# adc-dac.net
KiCad netlist of a schematic drawn in Altium Designer
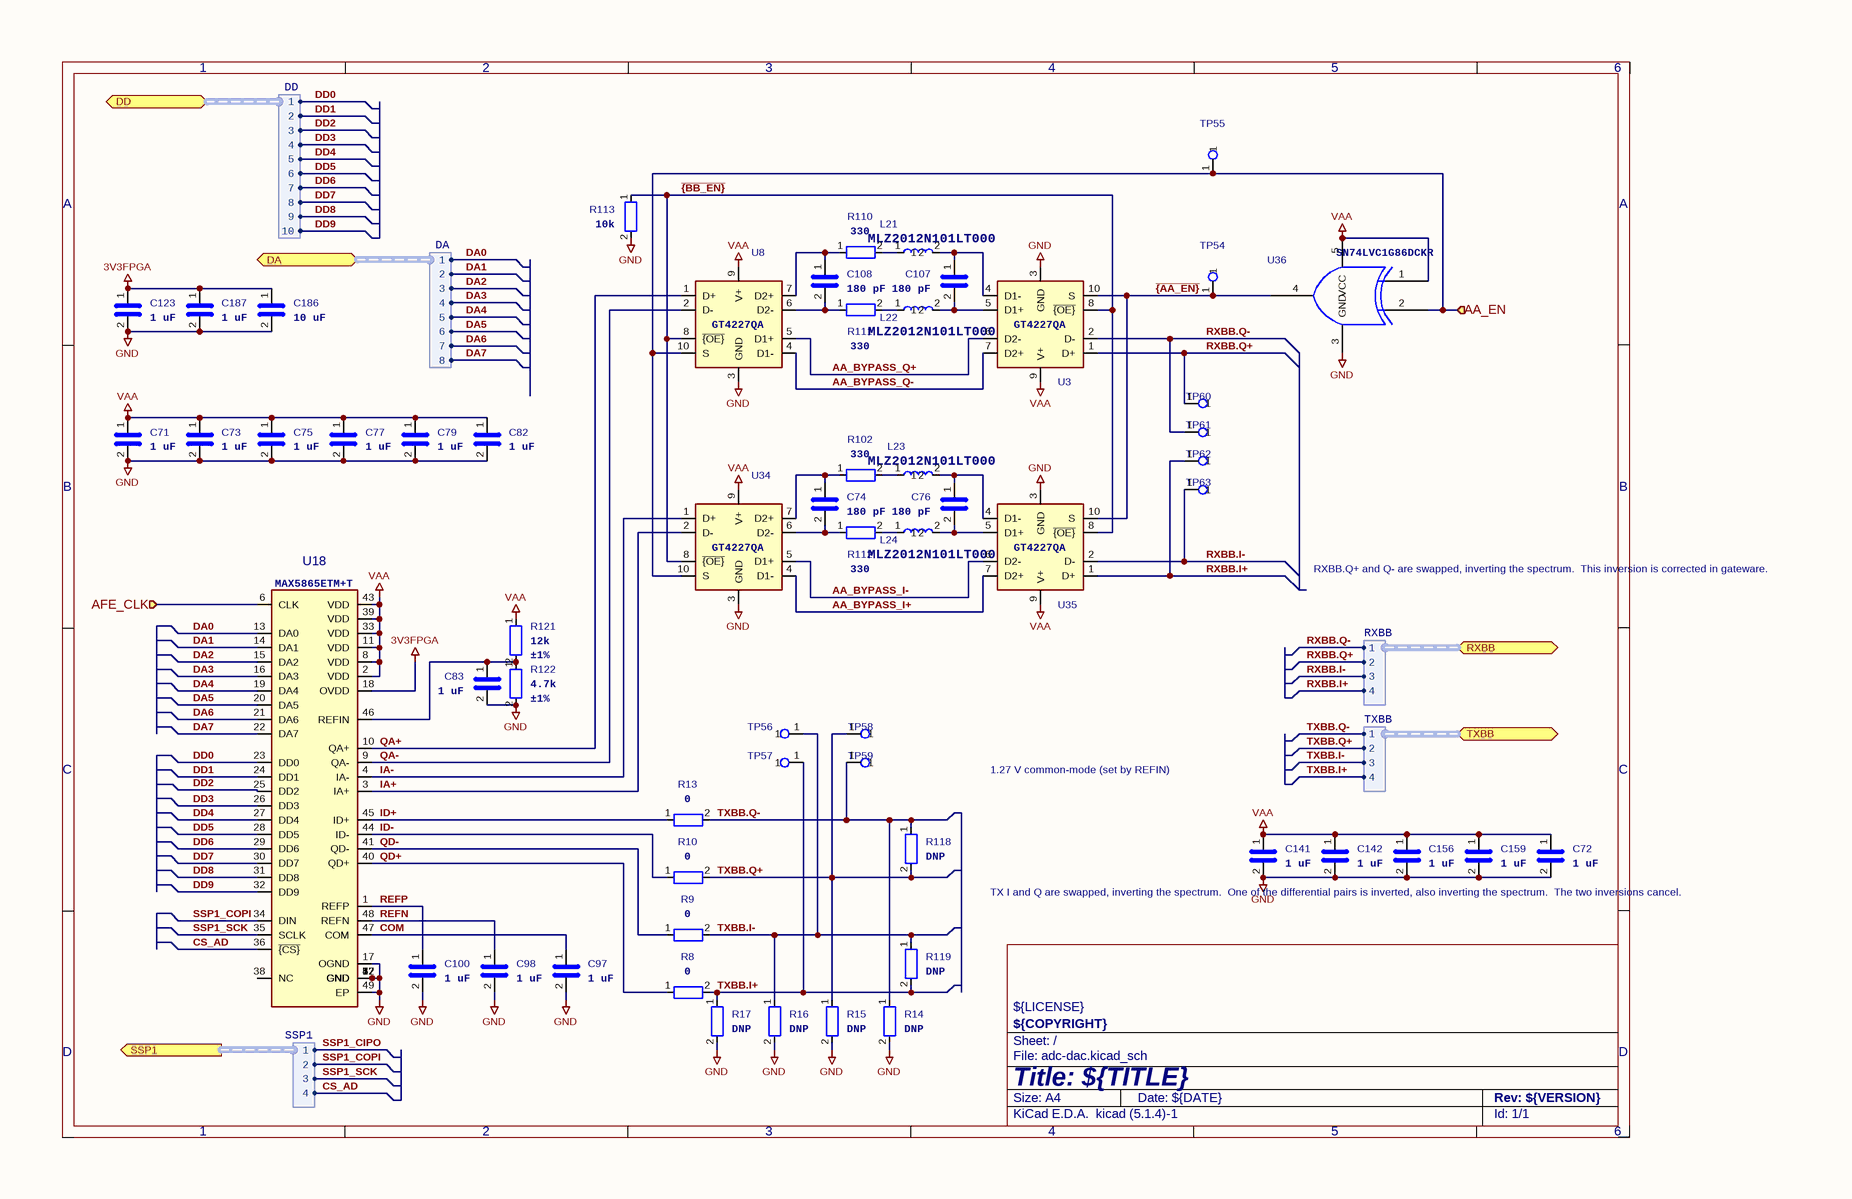
[diagram p0: adc-dac.SchDoc]

(export (version "E")
  (design (tool "Eeschema 10.0.6"))
  (components
    (comp (ref "C71")
      (value "1 uF")
      (footprint "C_0201_0603Metric")
      (fields (field (name "MANUFACTURER") "Murata") (field (name "PART NUMBER") "GRM033R61A105ME44D"))
      (libsource (lib "Device") (part "C"))
    )
    (comp (ref "C72")
      (value "1 uF")
      (footprint "C_0201_0603Metric")
      (fields (field (name "MANUFACTURER") "Murata") (field (name "PART NUMBER") "GRM033R61A105ME44D"))
      (libsource (lib "Device") (part "C"))
    )
    (comp (ref "C73")
      (value "1 uF")
      (footprint "C_0201_0603Metric")
      (fields (field (name "MANUFACTURER") "Murata") (field (name "PART NUMBER") "GRM033R61A105ME44D"))
      (libsource (lib "Device") (part "C"))
    )
    (comp (ref "C74")
      (value "180 pF")
      (footprint "C_0201_0603Metric")
      (fields (field (name "MANUFACTURER") "Murata") (field (name "PART NUMBER") "GRM0335C1H181JA01D"))
      (libsource (lib "Device") (part "C"))
    )
    (comp (ref "C75")
      (value "1 uF")
      (footprint "C_0201_0603Metric")
      (fields (field (name "MANUFACTURER") "Murata") (field (name "PART NUMBER") "GRM033R61A105ME44D"))
      (libsource (lib "Device") (part "C"))
    )
    (comp (ref "C76")
      (value "180 pF")
      (footprint "C_0201_0603Metric")
      (fields (field (name "MANUFACTURER") "Murata") (field (name "PART NUMBER") "GRM0335C1H181JA01D"))
      (libsource (lib "Device") (part "C"))
    )
    (comp (ref "C77")
      (value "1 uF")
      (footprint "C_0201_0603Metric")
      (fields (field (name "MANUFACTURER") "Murata") (field (name "PART NUMBER") "GRM033R61A105ME44D"))
      (libsource (lib "Device") (part "C"))
    )
    (comp (ref "C79")
      (value "1 uF")
      (footprint "C_0201_0603Metric")
      (fields (field (name "MANUFACTURER") "Murata") (field (name "PART NUMBER") "GRM033R61A105ME44D"))
      (libsource (lib "Device") (part "C"))
    )
    (comp (ref "C82")
      (value "1 uF")
      (footprint "C_0201_0603Metric")
      (fields (field (name "MANUFACTURER") "Murata") (field (name "PART NUMBER") "GRM033R61A105ME44D"))
      (libsource (lib "Device") (part "C"))
    )
    (comp (ref "C83")
      (value "1 uF")
      (footprint "C_0201_0603Metric")
      (fields (field (name "MANUFACTURER") "Murata") (field (name "PART NUMBER") "GRM033R61A105ME44D"))
      (libsource (lib "Device") (part "C"))
    )
    (comp (ref "C97")
      (value "1 uF")
      (footprint "C_0201_0603Metric")
      (fields (field (name "MANUFACTURER") "Murata") (field (name "PART NUMBER") "GRM033R61A105ME44D"))
      (libsource (lib "Device") (part "C"))
    )
    (comp (ref "C98")
      (value "1 uF")
      (footprint "C_0201_0603Metric")
      (fields (field (name "MANUFACTURER") "Murata") (field (name "PART NUMBER") "GRM033R61A105ME44D"))
      (libsource (lib "Device") (part "C"))
    )
    (comp (ref "C100")
      (value "1 uF")
      (footprint "C_0201_0603Metric")
      (fields (field (name "MANUFACTURER") "Murata") (field (name "PART NUMBER") "GRM033R61A105ME44D"))
      (libsource (lib "Device") (part "C"))
    )
    (comp (ref "C107")
      (value "180 pF")
      (footprint "C_0201_0603Metric")
      (fields (field (name "MANUFACTURER") "Murata") (field (name "PART NUMBER") "GRM0335C1H181JA01D"))
      (libsource (lib "Device") (part "C"))
    )
    (comp (ref "C108")
      (value "180 pF")
      (footprint "C_0201_0603Metric")
      (fields (field (name "MANUFACTURER") "Murata") (field (name "PART NUMBER") "GRM0335C1H181JA01D"))
      (libsource (lib "Device") (part "C"))
    )
    (comp (ref "C123")
      (value "1 uF")
      (footprint "C_0201_0603Metric")
      (fields (field (name "MANUFACTURER") "Murata") (field (name "PART NUMBER") "GRM033R61A105ME44D"))
      (libsource (lib "Device") (part "C"))
    )
    (comp (ref "C141")
      (value "1 uF")
      (footprint "C_0201_0603Metric")
      (fields (field (name "MANUFACTURER") "Murata") (field (name "PART NUMBER") "GRM033R61A105ME44D"))
      (libsource (lib "Device") (part "C"))
    )
    (comp (ref "C142")
      (value "1 uF")
      (footprint "C_0201_0603Metric")
      (fields (field (name "MANUFACTURER") "Murata") (field (name "PART NUMBER") "GRM033R61A105ME44D"))
      (libsource (lib "Device") (part "C"))
    )
    (comp (ref "C156")
      (value "1 uF")
      (footprint "C_0201_0603Metric")
      (fields (field (name "MANUFACTURER") "Murata") (field (name "PART NUMBER") "GRM033R61A105ME44D"))
      (libsource (lib "Device") (part "C"))
    )
    (comp (ref "C159")
      (value "1 uF")
      (footprint "C_0201_0603Metric")
      (fields (field (name "MANUFACTURER") "Murata") (field (name "PART NUMBER") "GRM033R61A105ME44D"))
      (libsource (lib "Device") (part "C"))
    )
    (comp (ref "C186")
      (value "10 uF")
      (footprint "C_0805_2012Metric")
      (fields (field (name "MANUFACTURER") "Samsung") (field (name "PART NUMBER") "CL21A106KOQNNNE"))
      (libsource (lib "Device") (part "C"))
    )
    (comp (ref "C187")
      (value "1 uF")
      (footprint "C_0201_0603Metric")
      (fields (field (name "MANUFACTURER") "Murata") (field (name "PART NUMBER") "GRM033R61A105ME44D"))
      (libsource (lib "Device") (part "C"))
    )
    (comp (ref "L21")
      (value "100 uH")
      (footprint "L_TDK_MLZ2012_h1.25mm")
      (fields (field (name "MANUFACTURER") "TDK") (field (name "PART NUMBER") "MLZ2012N101LT000"))
      (libsource (lib "Device") (part "L"))
    )
    (comp (ref "L22")
      (value "100 uH")
      (footprint "L_TDK_MLZ2012_h1.25mm")
      (fields (field (name "MANUFACTURER") "TDK") (field (name "PART NUMBER") "MLZ2012N101LT000"))
      (libsource (lib "Device") (part "L"))
    )
    (comp (ref "L23")
      (value "100 uH")
      (footprint "L_TDK_MLZ2012_h1.25mm")
      (fields (field (name "MANUFACTURER") "TDK") (field (name "PART NUMBER") "MLZ2012N101LT000"))
      (libsource (lib "Device") (part "L"))
    )
    (comp (ref "L24")
      (value "100 uH")
      (footprint "L_TDK_MLZ2012_h1.25mm")
      (fields (field (name "MANUFACTURER") "TDK") (field (name "PART NUMBER") "MLZ2012N101LT000"))
      (libsource (lib "Device") (part "L"))
    )
    (comp (ref "R8")
      (value "0")
      (footprint "R_0201_0603Metric")
      (fields (field (name "MANUFACTURER") "Yageo") (field (name "PART NUMBER") "RC0201JR-070RL"))
      (libsource (lib "") (part "R_1"))
    )
    (comp (ref "R9")
      (value "0")
      (footprint "R_0201_0603Metric")
      (fields (field (name "MANUFACTURER") "Yageo") (field (name "PART NUMBER") "RC0201JR-070RL"))
      (libsource (lib "") (part "R_1"))
    )
    (comp (ref "R10")
      (value "0")
      (footprint "R_0201_0603Metric")
      (fields (field (name "MANUFACTURER") "Yageo") (field (name "PART NUMBER") "RC0201JR-070RL"))
      (libsource (lib "") (part "R_1"))
    )
    (comp (ref "R13")
      (value "0")
      (footprint "R_0201_0603Metric")
      (fields (field (name "MANUFACTURER") "Yageo") (field (name "PART NUMBER") "RC0201JR-070RL"))
      (libsource (lib "") (part "R_1"))
    )
    (comp (ref "R14") (value "DNP") (footprint "R_0201_0603Metric") (libsource (lib "Device") (part "R")))
    (comp (ref "R15") (value "DNP") (footprint "R_0201_0603Metric") (libsource (lib "Device") (part "R")))
    (comp (ref "R16") (value "DNP") (footprint "R_0201_0603Metric") (libsource (lib "Device") (part "R")))
    (comp (ref "R17") (value "DNP") (footprint "R_0201_0603Metric") (libsource (lib "Device") (part "R")))
    (comp (ref "R102")
      (value "330")
      (footprint "R_0201_0603Metric")
      (fields (field (name "MANUFACTURER") "Yageo") (field (name "PART NUMBER") "RC0201JR-07330RL"))
      (libsource (lib "") (part "R_1"))
    )
    (comp (ref "R110")
      (value "330")
      (footprint "R_0201_0603Metric")
      (fields (field (name "MANUFACTURER") "Yageo") (field (name "PART NUMBER") "RC0201JR-07330RL"))
      (libsource (lib "") (part "R_1"))
    )
    (comp (ref "R111")
      (value "330")
      (footprint "R_0201_0603Metric")
      (fields (field (name "MANUFACTURER") "Yageo") (field (name "PART NUMBER") "RC0201JR-07330RL"))
      (libsource (lib "") (part "R_1"))
    )
    (comp (ref "R112")
      (value "330")
      (footprint "R_0201_0603Metric")
      (fields (field (name "MANUFACTURER") "Yageo") (field (name "PART NUMBER") "RC0201JR-07330RL"))
      (libsource (lib "") (part "R_1"))
    )
    (comp (ref "R113")
      (value "10k")
      (footprint "R_0402_1005Metric")
      (fields (field (name "MANUFACTURER") "Yageo") (field (name "PART NUMBER") "RC0402JR-0710KL"))
      (libsource (lib "") (part "R_2"))
    )
    (comp (ref "R118") (value "DNP") (footprint "R_0201_0603Metric") (libsource (lib "Device") (part "R")))
    (comp (ref "R119") (value "DNP") (footprint "R_0201_0603Metric") (libsource (lib "Device") (part "R")))
    (comp (ref "R121")
      (value "12k")
      (footprint "R_0201_0603Metric")
      (fields
        (field (name "MANUFACTURER") "Yageo")
        (field (name "PART NUMBER") "RC0201FR-0712KL")
        (field (name "TOLERANCE") "±1%")
      )
      (libsource (lib "") (part "R_2"))
    )
    (comp (ref "R122")
      (value "4.7k")
      (footprint "R_0201_0603Metric")
      (fields
        (field (name "MANUFACTURER") "Yageo")
        (field (name "PART NUMBER") "RC0201FR-074K7L")
        (field (name "TOLERANCE") "±1%")
      )
      (libsource (lib "Device") (part "R"))
    )
    (comp (ref "TP54")
      (value "TestPoint")
      (footprint "TestPoint_Pad_D1.0mm")
      (libsource (lib "Connector") (part "TestPoint"))
    )
    (comp (ref "TP55")
      (value "TestPoint")
      (footprint "TestPoint_Pad_D1.0mm")
      (libsource (lib "Connector") (part "TestPoint"))
    )
    (comp (ref "TP56")
      (value "TestPoint")
      (footprint "TestPoint_Pad_D1.0mm")
      (libsource (lib "Connector") (part "TestPoint"))
    )
    (comp (ref "TP57")
      (value "TestPoint")
      (footprint "TestPoint_Pad_D1.0mm")
      (libsource (lib "Connector") (part "TestPoint"))
    )
    (comp (ref "TP58")
      (value "TestPoint")
      (footprint "TestPoint_Pad_D1.0mm")
      (libsource (lib "Connector") (part "TestPoint"))
    )
    (comp (ref "TP59")
      (value "TestPoint")
      (footprint "TestPoint_Pad_D1.0mm")
      (libsource (lib "Connector") (part "TestPoint"))
    )
    (comp (ref "TP60")
      (value "TestPoint")
      (footprint "TestPoint_Pad_D1.0mm")
      (libsource (lib "Connector") (part "TestPoint"))
    )
    (comp (ref "TP61")
      (value "TestPoint")
      (footprint "TestPoint_Pad_D1.0mm")
      (libsource (lib "Connector") (part "TestPoint"))
    )
    (comp (ref "TP62")
      (value "TestPoint")
      (footprint "TestPoint_Pad_D1.0mm")
      (libsource (lib "Connector") (part "TestPoint"))
    )
    (comp (ref "TP63")
      (value "TestPoint")
      (footprint "TestPoint_Pad_D1.0mm")
      (libsource (lib "Connector") (part "TestPoint"))
    )
    (comp (ref "U3")
      (value "GT4227")
      (footprint "GTIC_UQFN-10_1.4x1.8mm_P0.4mm")
      (fields (field (name "MANUFACTURER") "GTIC") (field (name "PART NUMBER") "GT4227QA"))
      (libsource (lib "praline") (part "GT4227QA"))
    )
    (comp (ref "U8")
      (value "GT4227")
      (footprint "GTIC_UQFN-10_1.4x1.8mm_P0.4mm")
      (fields (field (name "MANUFACTURER") "GTIC") (field (name "PART NUMBER") "GT4227QA"))
      (libsource (lib "") (part "GT4227QA_1"))
    )
    (comp (ref "U18")
      (value "MAX5865")
      (footprint "QFN-48-1EP_7x7mm_P0.5mm_EP5.3x5.3mm_ThermalVias")
      (fields (field (name "MANUFACTURER") "Maxim") (field (name "PART NUMBER") "MAX5865ETM+T"))
      (libsource (lib "praline") (part "MAX5864"))
    )
    (comp (ref "U34")
      (value "GT4227")
      (footprint "GTIC_UQFN-10_1.4x1.8mm_P0.4mm")
      (fields (field (name "MANUFACTURER") "GTIC") (field (name "PART NUMBER") "GT4227QA"))
      (libsource (lib "") (part "GT4227QA_1"))
    )
    (comp (ref "U35")
      (value "GT4227")
      (footprint "GTIC_UQFN-10_1.4x1.8mm_P0.4mm")
      (fields (field (name "MANUFACTURER") "GTIC") (field (name "PART NUMBER") "GT4227QA"))
      (libsource (lib "praline") (part "GT4227QA"))
    )
    (comp (ref "U36")
      (value "74LVC1G86")
      (footprint "SOT-353_SC-70-5")
      (fields (field (name "MANUFACTURER") "UMW") (field (name "PART NUMBER") "SN74LVC1G86DCKR"))
      (libsource (lib "74xGxx") (part "74LVC1G86"))
    )
  )
  (nets
    (net (code "6") (name "/AA_BYPASS_I+") (class "Default")
      (node (ref "U34") (pin "4") (pinfunction "D1-_4") (pintype "passive"))
      (node (ref "U35") (pin "7") (pinfunction "D2+_7") (pintype "passive"))
    )
    (net (code "7") (name "/AA_BYPASS_I-") (class "Default")
      (node (ref "U34") (pin "5") (pinfunction "D1+_5") (pintype "passive"))
      (node (ref "U35") (pin "6") (pinfunction "D2-_6") (pintype "passive"))
    )
    (net (code "8") (name "/AA_BYPASS_Q+") (class "Default")
      (node (ref "U3") (pin "6") (pinfunction "D2-_6") (pintype "passive"))
      (node (ref "U8") (pin "5") (pinfunction "D1+_5") (pintype "passive"))
    )
    (net (code "9") (name "/AA_BYPASS_Q-") (class "Default")
      (node (ref "U3") (pin "7") (pinfunction "D2+_7") (pintype "passive"))
      (node (ref "U8") (pin "4") (pinfunction "D1-_4") (pintype "passive"))
    )
    (net (code "10") (name "/AA_EN") (class "Default")
      (node (ref "TP55") (pin "1") (pinfunction "1_1") (pintype "passive"))
      (node (ref "U34") (pin "10") (pinfunction "S_10") (pintype "passive"))
      (node (ref "U36") (pin "2") (pinfunction "2_2") (pintype "passive"))
      (node (ref "U8") (pin "10") (pinfunction "S_10") (pintype "passive"))
    )
    (net (code "11") (name "/AFE_CLK") (class "Default")
      (node (ref "U18") (pin "6") (pinfunction "CLK_6") (pintype "passive"))
    )
    (net (code "12") (name "/COM") (class "Default")
      (node (ref "C97") (pin "1") (pinfunction "1_1") (pintype "passive"))
      (node (ref "U18") (pin "47") (pinfunction "COM_47") (pintype "passive"))
    )
    (net (code "13") (name "/CS_AD") (class "Default")
      (node (ref "U18") (pin "36") (pinfunction "~{{CS}}_36") (pintype "passive"))
    )
    (net (code "14") (name "/DA0") (class "Default")
      (node (ref "U18") (pin "13") (pinfunction "DA0_13") (pintype "passive"))
    )
    (net (code "15") (name "/DA1") (class "Default")
      (node (ref "U18") (pin "14") (pinfunction "DA1_14") (pintype "passive"))
    )
    (net (code "16") (name "/DA2") (class "Default")
      (node (ref "U18") (pin "15") (pinfunction "DA2_15") (pintype "passive"))
    )
    (net (code "17") (name "/DA3") (class "Default")
      (node (ref "U18") (pin "16") (pinfunction "DA3_16") (pintype "passive"))
    )
    (net (code "18") (name "/DA4") (class "Default")
      (node (ref "U18") (pin "19") (pinfunction "DA4_19") (pintype "passive"))
    )
    (net (code "19") (name "/DA5") (class "Default")
      (node (ref "U18") (pin "20") (pinfunction "DA5_20") (pintype "passive"))
    )
    (net (code "20") (name "/DA6") (class "Default")
      (node (ref "U18") (pin "21") (pinfunction "DA6_21") (pintype "passive"))
    )
    (net (code "21") (name "/DA7") (class "Default")
      (node (ref "U18") (pin "22") (pinfunction "DA7_22") (pintype "passive"))
    )
    (net (code "22") (name "/DD0") (class "Default")
      (node (ref "U18") (pin "23") (pinfunction "DD0_23") (pintype "passive"))
    )
    (net (code "23") (name "/DD1") (class "Default")
      (node (ref "U18") (pin "24") (pinfunction "DD1_24") (pintype "passive"))
    )
    (net (code "24") (name "/DD2") (class "Default")
      (node (ref "U18") (pin "25") (pinfunction "DD2_25") (pintype "passive"))
    )
    (net (code "25") (name "/DD3") (class "Default")
      (node (ref "U18") (pin "26") (pinfunction "DD3_26") (pintype "passive"))
    )
    (net (code "26") (name "/DD4") (class "Default")
      (node (ref "U18") (pin "27") (pinfunction "DD4_27") (pintype "passive"))
    )
    (net (code "27") (name "/DD5") (class "Default")
      (node (ref "U18") (pin "28") (pinfunction "DD5_28") (pintype "passive"))
    )
    (net (code "28") (name "/DD6") (class "Default")
      (node (ref "U18") (pin "29") (pinfunction "DD6_29") (pintype "passive"))
    )
    (net (code "29") (name "/DD7") (class "Default")
      (node (ref "U18") (pin "30") (pinfunction "DD7_30") (pintype "passive"))
    )
    (net (code "30") (name "/DD8") (class "Default")
      (node (ref "U18") (pin "31") (pinfunction "DD8_31") (pintype "passive"))
    )
    (net (code "31") (name "/DD9") (class "Default")
      (node (ref "U18") (pin "32") (pinfunction "DD9_32") (pintype "passive"))
    )
    (net (code "32") (name "/IA+") (class "Default")
      (node (ref "U18") (pin "3") (pinfunction "IA+_3") (pintype "passive"))
      (node (ref "U34") (pin "2") (pinfunction "D-_2") (pintype "passive"))
    )
    (net (code "33") (name "/IA-") (class "Default")
      (node (ref "U18") (pin "4") (pinfunction "IA-_4") (pintype "passive"))
      (node (ref "U34") (pin "1") (pinfunction "D+_1") (pintype "passive"))
    )
    (net (code "34") (name "/ID+") (class "Default")
      (node (ref "R13") (pin "1") (pinfunction "1_1") (pintype "passive"))
      (node (ref "U18") (pin "45") (pinfunction "ID+_45") (pintype "passive"))
    )
    (net (code "35") (name "/ID-") (class "Default")
      (node (ref "R10") (pin "1") (pinfunction "1_1") (pintype "passive"))
      (node (ref "U18") (pin "44") (pinfunction "ID-_44") (pintype "passive"))
    )
    (net (code "36") (name "/QA+") (class "Default")
      (node (ref "U18") (pin "10") (pinfunction "QA+_10") (pintype "passive"))
      (node (ref "U8") (pin "1") (pinfunction "D+_1") (pintype "passive"))
    )
    (net (code "37") (name "/QA-") (class "Default")
      (node (ref "U18") (pin "9") (pinfunction "QA-_9") (pintype "passive"))
      (node (ref "U8") (pin "2") (pinfunction "D-_2") (pintype "passive"))
    )
    (net (code "38") (name "/QD+") (class "Default")
      (node (ref "R8") (pin "1") (pinfunction "1_1") (pintype "passive"))
      (node (ref "U18") (pin "40") (pinfunction "QD+_40") (pintype "passive"))
    )
    (net (code "39") (name "/QD-") (class "Default")
      (node (ref "R9") (pin "1") (pinfunction "1_1") (pintype "passive"))
      (node (ref "U18") (pin "41") (pinfunction "QD-_41") (pintype "passive"))
    )
    (net (code "40") (name "/REFN") (class "Default")
      (node (ref "C98") (pin "1") (pinfunction "1_1") (pintype "passive"))
      (node (ref "U18") (pin "48") (pinfunction "REFN_48") (pintype "passive"))
    )
    (net (code "41") (name "/REFP") (class "Default")
      (node (ref "C100") (pin "1") (pinfunction "1_1") (pintype "passive"))
      (node (ref "U18") (pin "1") (pinfunction "REFP_1") (pintype "passive"))
    )
    (net (code "42") (name "/RXBB.I+") (class "Default")
      (node (ref "TP62") (pin "1") (pinfunction "1_1") (pintype "passive"))
      (node (ref "U35") (pin "1") (pinfunction "D+_1") (pintype "passive"))
    )
    (net (code "43") (name "/RXBB.I-") (class "Default")
      (node (ref "TP63") (pin "1") (pinfunction "1_1") (pintype "passive"))
      (node (ref "U35") (pin "2") (pinfunction "D-_2") (pintype "passive"))
    )
    (net (code "44") (name "/RXBB.Q+") (class "Default")
      (node (ref "TP60") (pin "1") (pinfunction "1_1") (pintype "passive"))
      (node (ref "U3") (pin "1") (pinfunction "D+_1") (pintype "passive"))
    )
    (net (code "45") (name "/RXBB.Q-") (class "Default")
      (node (ref "TP61") (pin "1") (pinfunction "1_1") (pintype "passive"))
      (node (ref "U3") (pin "2") (pinfunction "D-_2") (pintype "passive"))
    )
    (net (code "47") (name "/SSP1_COPI") (class "Default")
      (node (ref "U18") (pin "34") (pinfunction "DIN_34") (pintype "passive"))
    )
    (net (code "48") (name "/SSP1_SCK") (class "Default")
      (node (ref "U18") (pin "35") (pinfunction "SCLK_35") (pintype "passive"))
    )
    (net (code "49") (name "/TXBB.I+") (class "Default")
      (node (ref "R119") (pin "2") (pinfunction "2_2") (pintype "passive"))
      (node (ref "R17") (pin "1") (pinfunction "1_1") (pintype "passive"))
      (node (ref "R8") (pin "2") (pinfunction "2_2") (pintype "passive"))
      (node (ref "TP57") (pin "1") (pinfunction "1_1") (pintype "passive"))
    )
    (net (code "50") (name "/TXBB.I-") (class "Default")
      (node (ref "R119") (pin "1") (pinfunction "1_1") (pintype "passive"))
      (node (ref "R16") (pin "1") (pinfunction "1_1") (pintype "passive"))
      (node (ref "R9") (pin "2") (pinfunction "2_2") (pintype "passive"))
      (node (ref "TP56") (pin "1") (pinfunction "1_1") (pintype "passive"))
    )
    (net (code "51") (name "/TXBB.Q+") (class "Default")
      (node (ref "R10") (pin "2") (pinfunction "2_2") (pintype "passive"))
      (node (ref "R118") (pin "2") (pinfunction "2_2") (pintype "passive"))
      (node (ref "R15") (pin "1") (pinfunction "1_1") (pintype "passive"))
      (node (ref "TP58") (pin "1") (pinfunction "1_1") (pintype "passive"))
    )
    (net (code "52") (name "/TXBB.Q-") (class "Default")
      (node (ref "R118") (pin "1") (pinfunction "1_1") (pintype "passive"))
      (node (ref "R13") (pin "2") (pinfunction "2_2") (pintype "passive"))
      (node (ref "R14") (pin "1") (pinfunction "1_1") (pintype "passive"))
      (node (ref "TP59") (pin "1") (pinfunction "1_1") (pintype "passive"))
    )
    (net (code "58") (name "/~{{AA_EN}}") (class "Default")
      (node (ref "TP54") (pin "1") (pinfunction "1_1") (pintype "passive"))
      (node (ref "U3") (pin "10") (pinfunction "S_10") (pintype "passive"))
      (node (ref "U35") (pin "10") (pinfunction "S_10") (pintype "passive"))
      (node (ref "U36") (pin "4") (pinfunction "4_4") (pintype "passive"))
    )
    (net (code "59") (name "/~{{BB_EN}}") (class "Default")
      (node (ref "R113") (pin "1") (pinfunction "1_1") (pintype "passive"))
      (node (ref "U3") (pin "8") (pinfunction "~{{OE}}_8") (pintype "passive"))
      (node (ref "U34") (pin "8") (pinfunction "~{{OE}}_8") (pintype "passive"))
      (node (ref "U35") (pin "8") (pinfunction "~{{OE}}_8") (pintype "passive"))
      (node (ref "U8") (pin "8") (pinfunction "~{{OE}}_8") (pintype "passive"))
    )
    (net (code "60") (name "3V3FPGA") (class "Default")
      (node (ref "C123") (pin "1") (pinfunction "1_1") (pintype "passive"))
      (node (ref "C186") (pin "1") (pinfunction "1_1") (pintype "passive"))
      (node (ref "C187") (pin "1") (pinfunction "1_1") (pintype "passive"))
      (node (ref "U18") (pin "18") (pinfunction "OVDD_18") (pintype "passive"))
    )
    (net (code "61") (name "GND") (class "Default")
      (node (ref "C100") (pin "2") (pinfunction "2_2") (pintype "passive"))
      (node (ref "C123") (pin "2") (pinfunction "2_2") (pintype "passive"))
      (node (ref "C141") (pin "2") (pinfunction "2_2") (pintype "passive"))
      (node (ref "C142") (pin "2") (pinfunction "2_2") (pintype "passive"))
      (node (ref "C156") (pin "2") (pinfunction "2_2") (pintype "passive"))
      (node (ref "C159") (pin "2") (pinfunction "2_2") (pintype "passive"))
      (node (ref "C186") (pin "2") (pinfunction "2_2") (pintype "passive"))
      (node (ref "C187") (pin "2") (pinfunction "2_2") (pintype "passive"))
      (node (ref "C71") (pin "2") (pinfunction "2_2") (pintype "passive"))
      (node (ref "C72") (pin "2") (pinfunction "2_2") (pintype "passive"))
      (node (ref "C73") (pin "2") (pinfunction "2_2") (pintype "passive"))
      (node (ref "C75") (pin "2") (pinfunction "2_2") (pintype "passive"))
      (node (ref "C77") (pin "2") (pinfunction "2_2") (pintype "passive"))
      (node (ref "C79") (pin "2") (pinfunction "2_2") (pintype "passive"))
      (node (ref "C82") (pin "2") (pinfunction "2_2") (pintype "passive"))
      (node (ref "C83") (pin "2") (pinfunction "2_2") (pintype "passive"))
      (node (ref "C97") (pin "2") (pinfunction "2_2") (pintype "passive"))
      (node (ref "C98") (pin "2") (pinfunction "2_2") (pintype "passive"))
      (node (ref "R113") (pin "2") (pinfunction "2_2") (pintype "passive"))
      (node (ref "R122") (pin "2") (pinfunction "2_2") (pintype "passive"))
      (node (ref "R14") (pin "2") (pinfunction "2_2") (pintype "passive"))
      (node (ref "R15") (pin "2") (pinfunction "2_2") (pintype "passive"))
      (node (ref "R16") (pin "2") (pinfunction "2_2") (pintype "passive"))
      (node (ref "R17") (pin "2") (pinfunction "2_2") (pintype "passive"))
      (node (ref "U18") (pin "12") (pinfunction "GND_12") (pintype "passive"))
      (node (ref "U18") (pin "17") (pinfunction "OGND_17") (pintype "passive"))
      (node (ref "U18") (pin "37") (pinfunction "GND_37") (pintype "passive"))
      (node (ref "U18") (pin "42") (pinfunction "GND_42") (pintype "passive"))
      (node (ref "U18") (pin "49") (pinfunction "EP_49") (pintype "passive"))
      (node (ref "U18") (pin "5") (pinfunction "GND_5") (pintype "passive"))
      (node (ref "U18") (pin "7") (pinfunction "GND_7") (pintype "passive"))
      (node (ref "U3") (pin "3") (pinfunction "GND_3") (pintype "passive"))
      (node (ref "U34") (pin "3") (pinfunction "GND_3") (pintype "passive"))
      (node (ref "U35") (pin "3") (pinfunction "GND_3") (pintype "passive"))
      (node (ref "U36") (pin "3") (pinfunction "GND_3") (pintype "passive"))
      (node (ref "U8") (pin "3") (pinfunction "GND_3") (pintype "passive"))
    )
    (net (code "62") (name "Net-(L21-Pad1)") (class "Default")
      (node (ref "L21") (pin "1") (pinfunction "1_1") (pintype "passive"))
      (node (ref "R110") (pin "2") (pinfunction "2_2") (pintype "passive"))
    )
    (net (code "63") (name "Net-(L22-Pad1)") (class "Default")
      (node (ref "L22") (pin "1") (pinfunction "1_1") (pintype "passive"))
      (node (ref "R111") (pin "2") (pinfunction "2_2") (pintype "passive"))
    )
    (net (code "64") (name "Net-(L23-Pad1)") (class "Default")
      (node (ref "L23") (pin "1") (pinfunction "1_1") (pintype "passive"))
      (node (ref "R102") (pin "2") (pinfunction "2_2") (pintype "passive"))
    )
    (net (code "65") (name "Net-(L24-Pad1)") (class "Default")
      (node (ref "L24") (pin "1") (pinfunction "1_1") (pintype "passive"))
      (node (ref "R112") (pin "2") (pinfunction "2_2") (pintype "passive"))
    )
    (net (code "66") (name "Net-(U3-D1+)") (class "Default")
      (node (ref "C107") (pin "2") (pinfunction "2_2") (pintype "passive"))
      (node (ref "L22") (pin "2") (pinfunction "2_2") (pintype "passive"))
      (node (ref "U3") (pin "5") (pinfunction "D1+_5") (pintype "passive"))
    )
    (net (code "67") (name "Net-(U3-D1-)") (class "Default")
      (node (ref "C107") (pin "1") (pinfunction "1_1") (pintype "passive"))
      (node (ref "L21") (pin "2") (pinfunction "2_2") (pintype "passive"))
      (node (ref "U3") (pin "4") (pinfunction "D1-_4") (pintype "passive"))
    )
    (net (code "68") (name "Net-(U8-D2+)") (class "Default")
      (node (ref "C108") (pin "1") (pinfunction "1_1") (pintype "passive"))
      (node (ref "R110") (pin "1") (pinfunction "1_1") (pintype "passive"))
      (node (ref "U8") (pin "7") (pinfunction "D2+_7") (pintype "passive"))
    )
    (net (code "69") (name "Net-(U8-D2-)") (class "Default")
      (node (ref "C108") (pin "2") (pinfunction "2_2") (pintype "passive"))
      (node (ref "R111") (pin "1") (pinfunction "1_1") (pintype "passive"))
      (node (ref "U8") (pin "6") (pinfunction "D2-_6") (pintype "passive"))
    )
    (net (code "70") (name "Net-(U18-REFIN)") (class "Default")
      (node (ref "C83") (pin "1") (pinfunction "1_1") (pintype "passive"))
      (node (ref "R121") (pin "2") (pinfunction "2_2") (pintype "passive"))
      (node (ref "R122") (pin "1") (pinfunction "1_1") (pintype "passive"))
      (node (ref "U18") (pin "46") (pinfunction "REFIN_46") (pintype "passive"))
    )
    (net (code "71") (name "Net-(U34-D2+)") (class "Default")
      (node (ref "C74") (pin "1") (pinfunction "1_1") (pintype "passive"))
      (node (ref "R102") (pin "1") (pinfunction "1_1") (pintype "passive"))
      (node (ref "U34") (pin "7") (pinfunction "D2+_7") (pintype "passive"))
    )
    (net (code "72") (name "Net-(U34-D2-)") (class "Default")
      (node (ref "C74") (pin "2") (pinfunction "2_2") (pintype "passive"))
      (node (ref "R112") (pin "1") (pinfunction "1_1") (pintype "passive"))
      (node (ref "U34") (pin "6") (pinfunction "D2-_6") (pintype "passive"))
    )
    (net (code "73") (name "Net-(U35-D1+)") (class "Default")
      (node (ref "C76") (pin "2") (pinfunction "2_2") (pintype "passive"))
      (node (ref "L24") (pin "2") (pinfunction "2_2") (pintype "passive"))
      (node (ref "U35") (pin "5") (pinfunction "D1+_5") (pintype "passive"))
    )
    (net (code "74") (name "Net-(U35-D1-)") (class "Default")
      (node (ref "C76") (pin "1") (pinfunction "1_1") (pintype "passive"))
      (node (ref "L23") (pin "2") (pinfunction "2_2") (pintype "passive"))
      (node (ref "U35") (pin "4") (pinfunction "D1-_4") (pintype "passive"))
    )
    (net (code "75") (name "VAA") (class "Default")
      (node (ref "C141") (pin "1") (pinfunction "1_1") (pintype "passive"))
      (node (ref "C142") (pin "1") (pinfunction "1_1") (pintype "passive"))
      (node (ref "C156") (pin "1") (pinfunction "1_1") (pintype "passive"))
      (node (ref "C159") (pin "1") (pinfunction "1_1") (pintype "passive"))
      (node (ref "C71") (pin "1") (pinfunction "1_1") (pintype "passive"))
      (node (ref "C72") (pin "1") (pinfunction "1_1") (pintype "passive"))
      (node (ref "C73") (pin "1") (pinfunction "1_1") (pintype "passive"))
      (node (ref "C75") (pin "1") (pinfunction "1_1") (pintype "passive"))
      (node (ref "C77") (pin "1") (pinfunction "1_1") (pintype "passive"))
      (node (ref "C79") (pin "1") (pinfunction "1_1") (pintype "passive"))
      (node (ref "C82") (pin "1") (pinfunction "1_1") (pintype "passive"))
      (node (ref "R121") (pin "1") (pinfunction "1_1") (pintype "passive"))
      (node (ref "U18") (pin "11") (pinfunction "VDD_11") (pintype "passive"))
      (node (ref "U18") (pin "2") (pinfunction "VDD_2") (pintype "passive"))
      (node (ref "U18") (pin "33") (pinfunction "VDD_33") (pintype "passive"))
      (node (ref "U18") (pin "39") (pinfunction "VDD_39") (pintype "passive"))
      (node (ref "U18") (pin "43") (pinfunction "VDD_43") (pintype "passive"))
      (node (ref "U18") (pin "8") (pinfunction "VDD_8") (pintype "passive"))
      (node (ref "U3") (pin "9") (pinfunction "V+_9") (pintype "passive"))
      (node (ref "U34") (pin "9") (pinfunction "V+_9") (pintype "passive"))
      (node (ref "U35") (pin "9") (pinfunction "V+_9") (pintype "passive"))
      (node (ref "U36") (pin "1") (pinfunction "1_1") (pintype "passive"))
      (node (ref "U36") (pin "5") (pinfunction "VCC_5") (pintype "passive"))
      (node (ref "U8") (pin "9") (pinfunction "V+_9") (pintype "passive"))
    )
    (net (code "76") (name "unconnected-(U18-NC-Pad38)") (class "Default")
      (node (ref "U18") (pin "38") (pinfunction "NC_38") (pintype "passive"))
    )
  )
)
